# nRF24L01_-_ATmega328_test_board.net
KiCad netlist of a schematic drawn in EAGLE
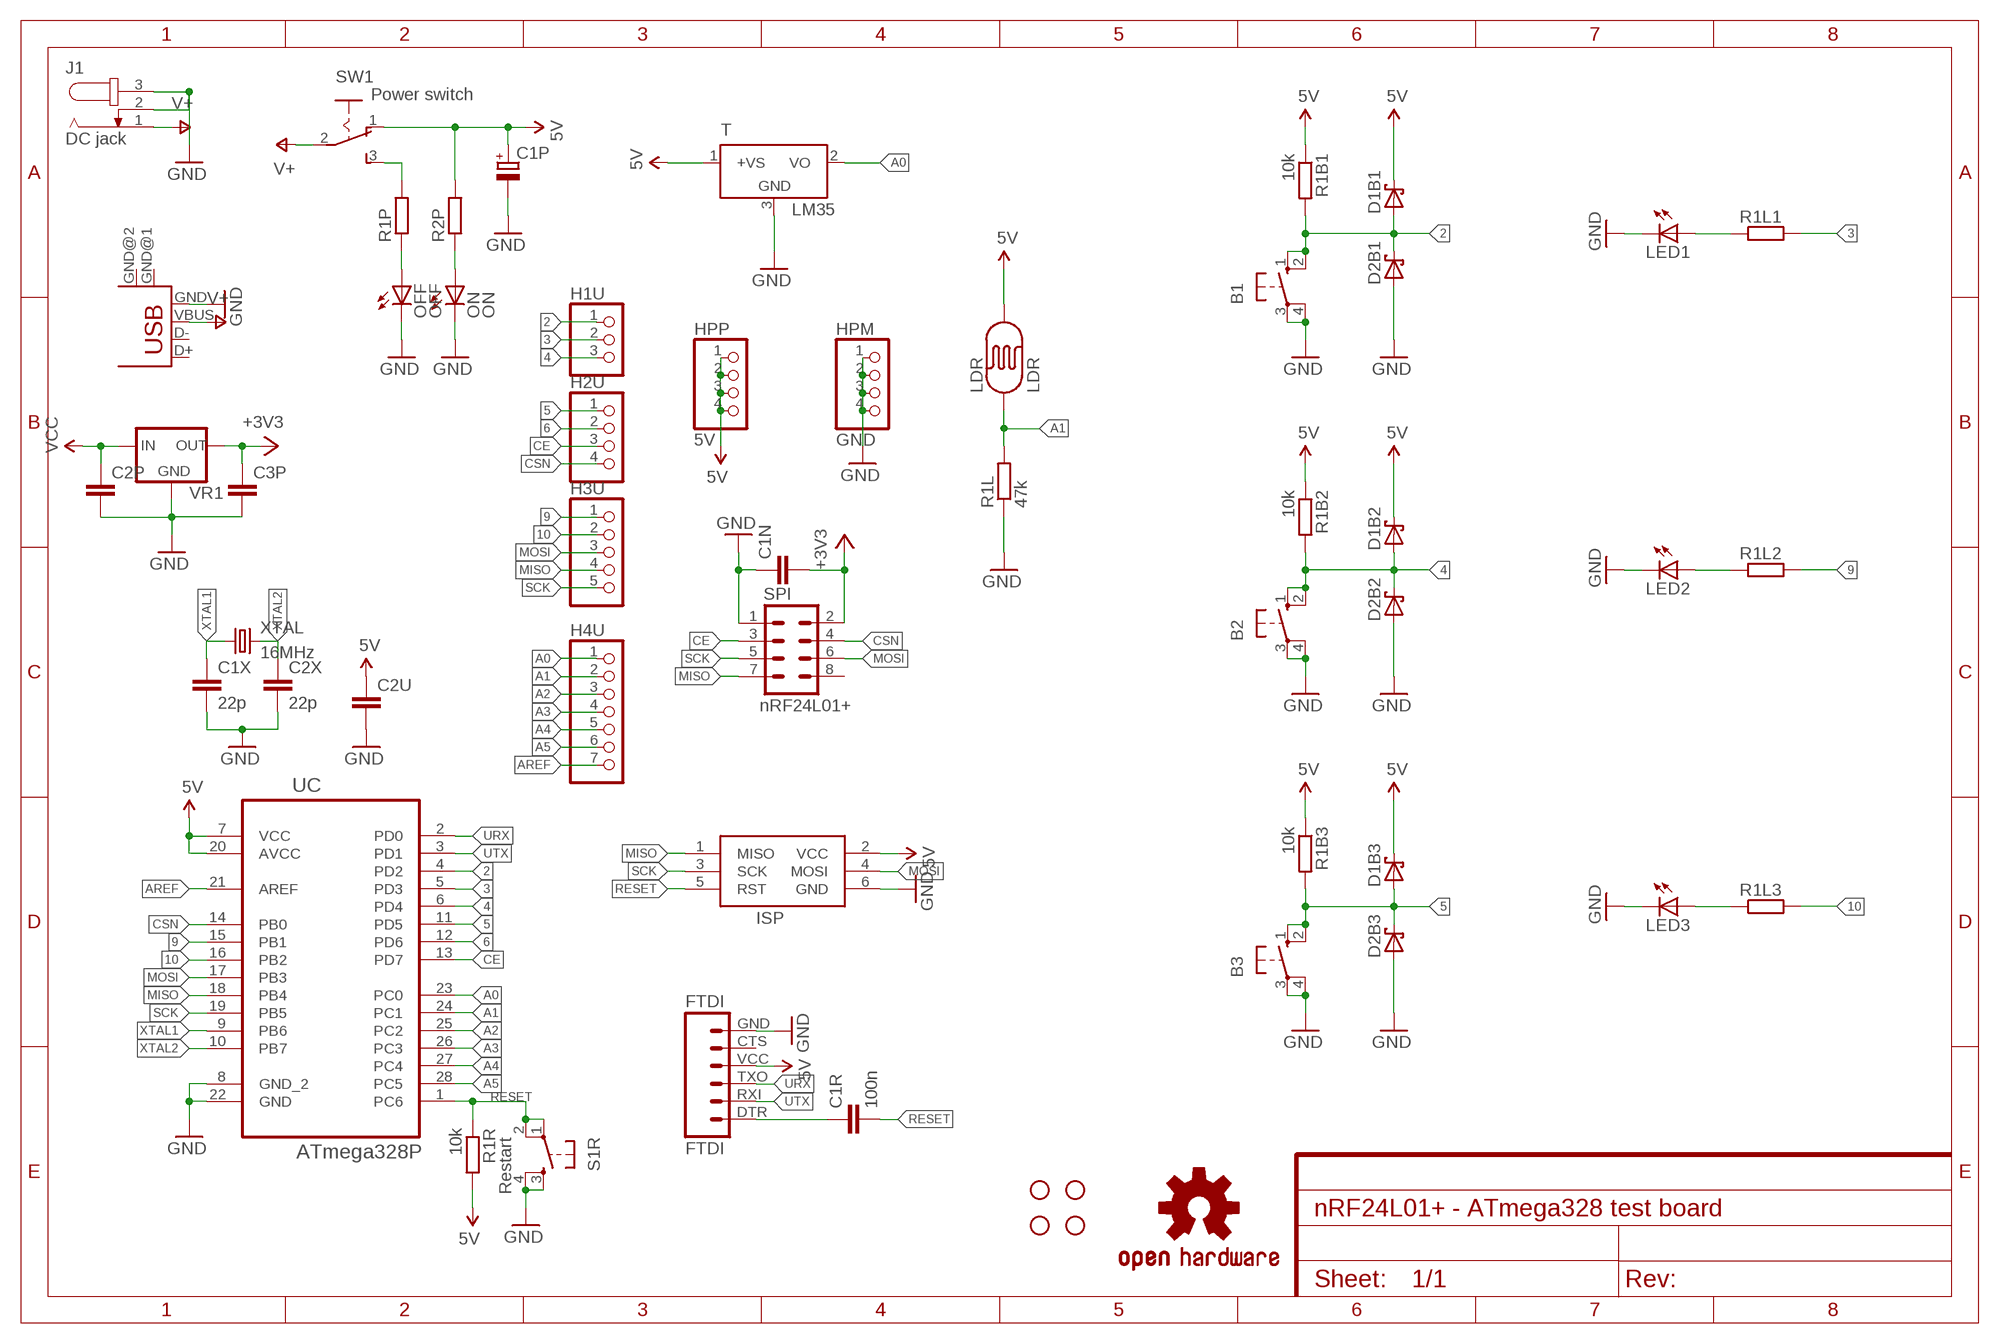
[diagram p0: schematic, sheet 1]

(export (version "E")
  (design (tool "Eeschema 10.0.6"))
  (components
    (comp (ref "B1")
      (value "40-XX")
      (footprint "eagle-import:B3F-40XX")
      (fields (field (name "MF") "OMRON COMPONENTS USA") (field (name "MPN") "B3F-4000"))
      (libsource (lib "eagle-import") (part "40-XX"))
    )
    (comp (ref "B2")
      (value "40-XX")
      (footprint "eagle-import:B3F-40XX")
      (fields (field (name "MF") "OMRON COMPONENTS USA") (field (name "MPN") "B3F-4000"))
      (libsource (lib "eagle-import") (part "40-XX"))
    )
    (comp (ref "B3")
      (value "40-XX")
      (footprint "eagle-import:B3F-40XX")
      (fields (field (name "MF") "OMRON COMPONENTS USA") (field (name "MPN") "B3F-4000"))
      (libsource (lib "eagle-import") (part "40-XX"))
    )
    (comp (ref "C1N")
      (value "C-EU050-025X075")
      (footprint "eagle-import:C050-025X075")
      (libsource (lib "eagle-import") (part "resistor_C-EU050-025X075"))
    )
    (comp (ref "C1P")
      (value "CPOL-EUE5-8.5")
      (footprint "eagle-import:E5-8,5")
      (libsource (lib "eagle-import") (part "CPOL-EUE5-8.5"))
    )
    (comp (ref "C1R")
      (value "100n")
      (footprint "eagle-import:C050-025X075")
      (libsource (lib "eagle-import") (part "resistor_C-EU050-025X075"))
    )
    (comp (ref "C1X")
      (value "22p")
      (footprint "eagle-import:C025-025X050")
      (libsource (lib "eagle-import") (part "resistor_C-EU025-025X050"))
    )
    (comp (ref "C2P")
      (value "C-EU050-025X075")
      (footprint "eagle-import:C050-025X075")
      (libsource (lib "eagle-import") (part "resistor_C-EU050-025X075"))
    )
    (comp (ref "C2U")
      (value "C-EU050-055X075")
      (footprint "eagle-import:C050-055X075")
      (libsource (lib "eagle-import") (part "C-EU050-055X075"))
    )
    (comp (ref "C2X")
      (value "22p")
      (footprint "eagle-import:C025-025X050")
      (libsource (lib "eagle-import") (part "resistor_C-EU025-025X050"))
    )
    (comp (ref "C3P")
      (value "C-EU050-025X075")
      (footprint "eagle-import:C050-025X075")
      (libsource (lib "eagle-import") (part "resistor_C-EU050-025X075"))
    )
    (comp (ref "D1B1")
      (value "SCHOTTKY-DIODEDO41-7")
      (footprint "eagle-import:DO41-7")
      (libsource (lib "eagle-import") (part "SCHOTTKY-DIODEDO41-7"))
    )
    (comp (ref "D1B2")
      (value "SCHOTTKY-DIODEDO41-7")
      (footprint "eagle-import:DO41-7")
      (libsource (lib "eagle-import") (part "SCHOTTKY-DIODEDO41-7"))
    )
    (comp (ref "D1B3")
      (value "SCHOTTKY-DIODEDO41-7")
      (footprint "eagle-import:DO41-7")
      (libsource (lib "eagle-import") (part "SCHOTTKY-DIODEDO41-7"))
    )
    (comp (ref "D2B1")
      (value "SCHOTTKY-DIODEDO41-7")
      (footprint "eagle-import:DO41-7")
      (libsource (lib "eagle-import") (part "SCHOTTKY-DIODEDO41-7"))
    )
    (comp (ref "D2B2")
      (value "SCHOTTKY-DIODEDO41-7")
      (footprint "eagle-import:DO41-7")
      (libsource (lib "eagle-import") (part "SCHOTTKY-DIODEDO41-7"))
    )
    (comp (ref "D2B3")
      (value "SCHOTTKY-DIODEDO41-7")
      (footprint "eagle-import:DO41-7")
      (libsource (lib "eagle-import") (part "SCHOTTKY-DIODEDO41-7"))
    )
    (comp (ref "FTDI")
      (value "FTDI")
      (footprint "eagle-import:FTDI_BASIC")
      (libsource (lib "eagle-import") (part "FTDI_BASICPTH"))
    )
    (comp (ref "H1")
      (value "STAND-OFF")
      (footprint "eagle-import:STAND-OFF")
      (libsource (lib "eagle-import") (part "STAND-OFF"))
    )
    (comp (ref "H1U")
      (value "PINHD-1X3")
      (footprint "eagle-import:1X03")
      (libsource (lib "eagle-import") (part "PINHD-1X3"))
    )
    (comp (ref "H2")
      (value "STAND-OFF")
      (footprint "eagle-import:STAND-OFF")
      (libsource (lib "eagle-import") (part "STAND-OFF"))
    )
    (comp (ref "H2U")
      (value "PINHD-1X4")
      (footprint "eagle-import:1X04")
      (libsource (lib "eagle-import") (part "PINHD-1X4"))
    )
    (comp (ref "H3")
      (value "STAND-OFF")
      (footprint "eagle-import:STAND-OFF")
      (libsource (lib "eagle-import") (part "STAND-OFF"))
    )
    (comp (ref "H3U")
      (value "PINHD-1X5")
      (footprint "eagle-import:1X05")
      (libsource (lib "eagle-import") (part "PINHD-1X5"))
    )
    (comp (ref "H4")
      (value "STAND-OFF")
      (footprint "eagle-import:STAND-OFF")
      (libsource (lib "eagle-import") (part "STAND-OFF"))
    )
    (comp (ref "H4U")
      (value "PINHD-1X7")
      (footprint "eagle-import:1X07")
      (libsource (lib "eagle-import") (part "PINHD-1X7"))
    )
    (comp (ref "HPM")
      (value "GND")
      (footprint "eagle-import:1X04")
      (libsource (lib "eagle-import") (part "PINHD-1X4"))
    )
    (comp (ref "HPP")
      (value "5V")
      (footprint "eagle-import:1X04")
      (libsource (lib "eagle-import") (part "PINHD-1X4"))
    )
    (comp (ref "ISP")
      (value "AVRISP-6")
      (footprint "eagle-import:AVRISP")
      (libsource (lib "eagle-import") (part "AVRISP-6"))
    )
    (comp (ref "J1")
      (value "DC jack")
      (footprint "eagle-import:SPC4078")
      (libsource (lib "eagle-import") (part "JACK-PLUG1"))
    )
    (comp (ref "J2")
      (value "USB mini")
      (footprint "eagle-import:USB-MB-H")
      (libsource (lib "eagle-import") (part "USB-MB-H"))
    )
    (comp (ref "LDR")
      (value "LDR")
      (footprint "eagle-import:PHOTOCELL")
      (libsource (lib "eagle-import") (part "PHOTOCELLPTH"))
    )
    (comp (ref "LED1")
      (value "LED5MM")
      (footprint "eagle-import:LED5MM")
      (libsource (lib "eagle-import") (part "LED5MM"))
    )
    (comp (ref "LED2")
      (value "LED5MM")
      (footprint "eagle-import:LED5MM")
      (libsource (lib "eagle-import") (part "LED5MM"))
    )
    (comp (ref "LED3")
      (value "LED5MM")
      (footprint "eagle-import:LED5MM")
      (libsource (lib "eagle-import") (part "LED5MM"))
    )
    (comp (ref "LOGO1")
      (value "OSHW-LOGOM-COPPER")
      (footprint "eagle-import:OSHW-LOGO-M_COPPER")
      (libsource (lib "eagle-import") (part "OSHW-LOGOM-COPPER"))
    )
    (comp (ref "OFF")
      (value "OFF")
      (footprint "eagle-import:LED3MM")
      (libsource (lib "eagle-import") (part "LED3MM"))
    )
    (comp (ref "ON")
      (value "ON")
      (footprint "eagle-import:LED3MM")
      (libsource (lib "eagle-import") (part "LED3MM"))
    )
    (comp (ref "R1B1")
      (value "10k")
      (footprint "eagle-import:0207_7")
      (libsource (lib "eagle-import") (part "R-EU_0207/7"))
    )
    (comp (ref "R1B2")
      (value "10k")
      (footprint "eagle-import:0207_7")
      (libsource (lib "eagle-import") (part "R-EU_0207/7"))
    )
    (comp (ref "R1B3")
      (value "10k")
      (footprint "eagle-import:0207_7")
      (libsource (lib "eagle-import") (part "R-EU_0207/7"))
    )
    (comp (ref "R1L")
      (value "47k")
      (footprint "eagle-import:0207_7")
      (libsource (lib "eagle-import") (part "R-EU_0207/7"))
    )
    (comp (ref "R1L1")
      (value "R-EU_0207/7")
      (footprint "eagle-import:0207_7")
      (libsource (lib "eagle-import") (part "R-EU_0207/7"))
    )
    (comp (ref "R1L2")
      (value "R-EU_0207/7")
      (footprint "eagle-import:0207_7")
      (libsource (lib "eagle-import") (part "R-EU_0207/7"))
    )
    (comp (ref "R1L3")
      (value "R-EU_0207/7")
      (footprint "eagle-import:0207_7")
      (libsource (lib "eagle-import") (part "R-EU_0207/7"))
    )
    (comp (ref "R1P")
      (value "R-EU_0207/7")
      (footprint "eagle-import:0207_7")
      (libsource (lib "eagle-import") (part "R-EU_0207/7"))
    )
    (comp (ref "R1R")
      (value "10k")
      (footprint "eagle-import:0207_7")
      (libsource (lib "eagle-import") (part "R-EU_0207/7"))
    )
    (comp (ref "R2P")
      (value "R-EU_0207/7")
      (footprint "eagle-import:0207_7")
      (libsource (lib "eagle-import") (part "R-EU_0207/7"))
    )
    (comp (ref "S1R")
      (value "Restart")
      (footprint "eagle-import:TACTILE-PTH")
      (libsource (lib "eagle-import") (part "TAC_SWITCHPTH"))
    )
    (comp (ref "SPI")
      (value "nRF24L01+")
      (footprint "eagle-import:2X4")
      (fields (field (name "MF") "OLIMEX") (field (name "MPN") "MOD-NRF24LR"))
      (libsource (lib "eagle-import") (part "M04X2"))
    )
    (comp (ref "SW1")
      (value "Power switch")
      (footprint "eagle-import:SWITCH_2MM")
      (libsource (lib "eagle-import") (part "SPDT_SWITCH_2MM"))
    )
    (comp (ref "T")
      (value "LM35")
      (footprint "eagle-import:TO92")
      (libsource (lib "eagle-import") (part "LM35CZ"))
    )
    (comp (ref "UC")
      (value "ATmega328P")
      (footprint "eagle-import:DIP254P762X457-28")
      (fields (field (name "MPN") "ATMEGA328P-PU"))
      (libsource (lib "eagle-import") (part "ATMEGA328P-PU"))
    )
    (comp (ref "VR1")
      (value "78LXX")
      (footprint "eagle-import:78LXX")
      (libsource (lib "eagle-import") (part "78LXX"))
    )
    (comp (ref "XTAL")
      (value "16MHz")
      (footprint "eagle-import:HC49_S")
      (libsource (lib "eagle-import") (part "CRYSTALHC49S"))
    )
  )
  (nets
    (net (code "1") (name "+3V3") (class "Default")
      (node (ref "C1N") (pin "2") (pinfunction "2_2") (pintype "passive"))
      (node (ref "C3P") (pin "1") (pinfunction "1_1") (pintype "passive"))
      (node (ref "SPI") (pin "2") (pinfunction "2_2") (pintype "passive"))
      (node (ref "VR1") (pin "OUT") (pinfunction "OUT_OUT") (pintype "passive"))
    )
    (net (code "2") (name "2") (class "Default")
      (node (ref "B1") (pin "1") (pinfunction "S_1") (pintype "passive"))
      (node (ref "B1") (pin "2") (pinfunction "S1_2") (pintype "passive"))
      (node (ref "D1B1") (pin "A") (pinfunction "A_A") (pintype "passive"))
      (node (ref "D2B1") (pin "C") (pinfunction "C_C") (pintype "passive"))
      (node (ref "H1U") (pin "1") (pinfunction "1_1") (pintype "passive"))
      (node (ref "R1B1") (pin "2") (pinfunction "2_2") (pintype "passive"))
      (node (ref "UC") (pin "4") (pinfunction "PD2_4") (pintype "bidirectional"))
    )
    (net (code "3") (name "3") (class "Default")
      (node (ref "H1U") (pin "2") (pinfunction "2_2") (pintype "passive"))
      (node (ref "R1L1") (pin "2") (pinfunction "2_2") (pintype "passive"))
      (node (ref "UC") (pin "5") (pinfunction "PD3_5") (pintype "bidirectional"))
    )
    (net (code "4") (name "4") (class "Default")
      (node (ref "B2") (pin "1") (pinfunction "S_1") (pintype "passive"))
      (node (ref "B2") (pin "2") (pinfunction "S1_2") (pintype "passive"))
      (node (ref "D1B2") (pin "A") (pinfunction "A_A") (pintype "passive"))
      (node (ref "D2B2") (pin "C") (pinfunction "C_C") (pintype "passive"))
      (node (ref "H1U") (pin "3") (pinfunction "3_3") (pintype "passive"))
      (node (ref "R1B2") (pin "2") (pinfunction "2_2") (pintype "passive"))
      (node (ref "UC") (pin "6") (pinfunction "PD4_6") (pintype "bidirectional"))
    )
    (net (code "5") (name "5") (class "Default")
      (node (ref "B3") (pin "1") (pinfunction "S_1") (pintype "passive"))
      (node (ref "B3") (pin "2") (pinfunction "S1_2") (pintype "passive"))
      (node (ref "D1B3") (pin "A") (pinfunction "A_A") (pintype "passive"))
      (node (ref "D2B3") (pin "C") (pinfunction "C_C") (pintype "passive"))
      (node (ref "H2U") (pin "1") (pinfunction "1_1") (pintype "passive"))
      (node (ref "R1B3") (pin "2") (pinfunction "2_2") (pintype "passive"))
      (node (ref "UC") (pin "11") (pinfunction "PD5_11") (pintype "bidirectional"))
    )
    (net (code "6") (name "5V") (class "Default")
      (node (ref "C1P") (pin "+") (pinfunction "+_+") (pintype "passive"))
      (node (ref "C2U") (pin "1") (pinfunction "1_1") (pintype "passive"))
      (node (ref "D1B1") (pin "C") (pinfunction "C_C") (pintype "passive"))
      (node (ref "D1B2") (pin "C") (pinfunction "C_C") (pintype "passive"))
      (node (ref "D1B3") (pin "C") (pinfunction "C_C") (pintype "passive"))
      (node (ref "FTDI") (pin "VCC") (pinfunction "4_VCC") (pintype "passive"))
      (node (ref "HPP") (pin "1") (pinfunction "1_1") (pintype "passive"))
      (node (ref "HPP") (pin "2") (pinfunction "2_2") (pintype "passive"))
      (node (ref "HPP") (pin "3") (pinfunction "3_3") (pintype "passive"))
      (node (ref "HPP") (pin "4") (pinfunction "4_4") (pintype "passive"))
      (node (ref "ISP") (pin "2") (pinfunction "VCC_2") (pintype "power_in"))
      (node (ref "LDR") (pin "2") (pinfunction "P$2_2") (pintype "bidirectional"))
      (node (ref "R1B1") (pin "1") (pinfunction "1_1") (pintype "passive"))
      (node (ref "R1B2") (pin "1") (pinfunction "1_1") (pintype "passive"))
      (node (ref "R1B3") (pin "1") (pinfunction "1_1") (pintype "passive"))
      (node (ref "R1R") (pin "2") (pinfunction "2_2") (pintype "passive"))
      (node (ref "R2P") (pin "2") (pinfunction "2_2") (pintype "passive"))
      (node (ref "SW1") (pin "1") (pinfunction "1_1") (pintype "passive"))
      (node (ref "T") (pin "1") (pinfunction "+VS_1") (pintype "input"))
      (node (ref "UC") (pin "20") (pinfunction "AVCC_20") (pintype "power_in"))
      (node (ref "UC") (pin "7") (pinfunction "VCC_7") (pintype "power_in"))
    )
    (net (code "7") (name "6") (class "Default")
      (node (ref "H2U") (pin "2") (pinfunction "2_2") (pintype "passive"))
      (node (ref "UC") (pin "12") (pinfunction "PD6_12") (pintype "bidirectional"))
    )
    (net (code "8") (name "9") (class "Default")
      (node (ref "H3U") (pin "1") (pinfunction "1_1") (pintype "passive"))
      (node (ref "R1L2") (pin "2") (pinfunction "2_2") (pintype "passive"))
      (node (ref "UC") (pin "15") (pinfunction "PB1_15") (pintype "bidirectional"))
    )
    (net (code "9") (name "10") (class "Default")
      (node (ref "H3U") (pin "2") (pinfunction "2_2") (pintype "passive"))
      (node (ref "R1L3") (pin "2") (pinfunction "2_2") (pintype "passive"))
      (node (ref "UC") (pin "16") (pinfunction "PB2_16") (pintype "bidirectional"))
    )
    (net (code "10") (name "A0") (class "Default")
      (node (ref "H4U") (pin "1") (pinfunction "1_1") (pintype "passive"))
      (node (ref "T") (pin "2") (pinfunction "VO_2") (pintype "input"))
      (node (ref "UC") (pin "23") (pinfunction "PC0_23") (pintype "bidirectional"))
    )
    (net (code "11") (name "A1") (class "Default")
      (node (ref "H4U") (pin "2") (pinfunction "2_2") (pintype "passive"))
      (node (ref "LDR") (pin "1") (pinfunction "P$1_1") (pintype "bidirectional"))
      (node (ref "R1L") (pin "2") (pinfunction "2_2") (pintype "passive"))
      (node (ref "UC") (pin "24") (pinfunction "PC1_24") (pintype "bidirectional"))
    )
    (net (code "12") (name "A2") (class "Default")
      (node (ref "H4U") (pin "3") (pinfunction "3_3") (pintype "passive"))
      (node (ref "UC") (pin "25") (pinfunction "PC2_25") (pintype "bidirectional"))
    )
    (net (code "13") (name "A3") (class "Default")
      (node (ref "H4U") (pin "4") (pinfunction "4_4") (pintype "passive"))
      (node (ref "UC") (pin "26") (pinfunction "PC3_26") (pintype "bidirectional"))
    )
    (net (code "14") (name "A4") (class "Default")
      (node (ref "H4U") (pin "5") (pinfunction "5_5") (pintype "passive"))
      (node (ref "UC") (pin "27") (pinfunction "PC4_27") (pintype "bidirectional"))
    )
    (net (code "15") (name "A5") (class "Default")
      (node (ref "H4U") (pin "6") (pinfunction "6_6") (pintype "passive"))
      (node (ref "UC") (pin "28") (pinfunction "PC5_28") (pintype "bidirectional"))
    )
    (net (code "16") (name "AREF") (class "Default")
      (node (ref "H4U") (pin "7") (pinfunction "7_7") (pintype "passive"))
      (node (ref "UC") (pin "21") (pinfunction "AREF_21") (pintype "input"))
    )
    (net (code "17") (name "CE") (class "Default")
      (node (ref "H2U") (pin "3") (pinfunction "3_3") (pintype "passive"))
      (node (ref "SPI") (pin "3") (pinfunction "3_3") (pintype "passive"))
      (node (ref "UC") (pin "13") (pinfunction "PD7_13") (pintype "bidirectional"))
    )
    (net (code "18") (name "CSN") (class "Default")
      (node (ref "H2U") (pin "4") (pinfunction "4_4") (pintype "passive"))
      (node (ref "SPI") (pin "4") (pinfunction "4_4") (pintype "passive"))
      (node (ref "UC") (pin "14") (pinfunction "PB0_14") (pintype "bidirectional"))
    )
    (net (code "19") (name "GND") (class "Default")
      (node (ref "B1") (pin "3") (pinfunction "P_3") (pintype "passive"))
      (node (ref "B1") (pin "4") (pinfunction "P1_4") (pintype "passive"))
      (node (ref "B2") (pin "3") (pinfunction "P_3") (pintype "passive"))
      (node (ref "B2") (pin "4") (pinfunction "P1_4") (pintype "passive"))
      (node (ref "B3") (pin "3") (pinfunction "P_3") (pintype "passive"))
      (node (ref "B3") (pin "4") (pinfunction "P1_4") (pintype "passive"))
      (node (ref "C1N") (pin "1") (pinfunction "1_1") (pintype "passive"))
      (node (ref "C1P") (pin "-") (pinfunction "-_-") (pintype "passive"))
      (node (ref "C1X") (pin "2") (pinfunction "2_2") (pintype "passive"))
      (node (ref "C2P") (pin "2") (pinfunction "2_2") (pintype "passive"))
      (node (ref "C2U") (pin "2") (pinfunction "2_2") (pintype "passive"))
      (node (ref "C2X") (pin "2") (pinfunction "2_2") (pintype "passive"))
      (node (ref "C3P") (pin "2") (pinfunction "2_2") (pintype "passive"))
      (node (ref "D2B1") (pin "A") (pinfunction "A_A") (pintype "passive"))
      (node (ref "D2B2") (pin "A") (pinfunction "A_A") (pintype "passive"))
      (node (ref "D2B3") (pin "A") (pinfunction "A_A") (pintype "passive"))
      (node (ref "FTDI") (pin "GND") (pinfunction "6_GND") (pintype "passive"))
      (node (ref "HPM") (pin "1") (pinfunction "1_1") (pintype "passive"))
      (node (ref "HPM") (pin "2") (pinfunction "2_2") (pintype "passive"))
      (node (ref "HPM") (pin "3") (pinfunction "3_3") (pintype "passive"))
      (node (ref "HPM") (pin "4") (pinfunction "4_4") (pintype "passive"))
      (node (ref "ISP") (pin "6") (pinfunction "GND_6") (pintype "power_in"))
      (node (ref "J1") (pin "2") (pinfunction "2_2") (pintype "passive"))
      (node (ref "J1") (pin "3") (pinfunction "3_3") (pintype "passive"))
      (node (ref "J2") (pin "GND") (pinfunction "GND_GND") (pintype "bidirectional"))
      (node (ref "LED1") (pin "K") (pinfunction "C_K") (pintype "passive"))
      (node (ref "LED2") (pin "K") (pinfunction "C_K") (pintype "passive"))
      (node (ref "LED3") (pin "K") (pinfunction "C_K") (pintype "passive"))
      (node (ref "OFF") (pin "K") (pinfunction "C_K") (pintype "passive"))
      (node (ref "ON") (pin "K") (pinfunction "C_K") (pintype "passive"))
      (node (ref "R1L") (pin "1") (pinfunction "1_1") (pintype "passive"))
      (node (ref "S1R") (pin "3") (pinfunction "3_3") (pintype "passive"))
      (node (ref "S1R") (pin "4") (pinfunction "4_4") (pintype "passive"))
      (node (ref "SPI") (pin "1") (pinfunction "1_1") (pintype "passive"))
      (node (ref "T") (pin "3") (pinfunction "GND_3") (pintype "power_in"))
      (node (ref "UC") (pin "22") (pinfunction "GND_22") (pintype "passive"))
      (node (ref "UC") (pin "8") (pinfunction "GND_2_8") (pintype "passive"))
      (node (ref "VR1") (pin "GND") (pinfunction "GND_GND") (pintype "input"))
    )
    (net (code "20") (name "MISO") (class "Default")
      (node (ref "H3U") (pin "4") (pinfunction "4_4") (pintype "passive"))
      (node (ref "ISP") (pin "1") (pinfunction "MISO_1") (pintype "input"))
      (node (ref "SPI") (pin "7") (pinfunction "7_7") (pintype "passive"))
      (node (ref "UC") (pin "18") (pinfunction "PB4_18") (pintype "bidirectional"))
    )
    (net (code "21") (name "MOSI") (class "Default")
      (node (ref "H3U") (pin "3") (pinfunction "3_3") (pintype "passive"))
      (node (ref "ISP") (pin "4") (pinfunction "MOSI_4") (pintype "output"))
      (node (ref "SPI") (pin "6") (pinfunction "6_6") (pintype "passive"))
      (node (ref "UC") (pin "17") (pinfunction "PB3_17") (pintype "bidirectional"))
    )
    (net (code "22") (name "Net-(FTDI-1)") (class "Default")
      (node (ref "C1R") (pin "1") (pinfunction "1_1") (pintype "passive"))
      (node (ref "FTDI") (pin "DTR") (pinfunction "1_DTR") (pintype "passive"))
    )
    (net (code "23") (name "Net-(LED1-PadA)") (class "Default")
      (node (ref "LED1") (pin "A") (pinfunction "A_A") (pintype "passive"))
      (node (ref "R1L1") (pin "1") (pinfunction "1_1") (pintype "passive"))
    )
    (net (code "24") (name "Net-(LED2-PadA)") (class "Default")
      (node (ref "LED2") (pin "A") (pinfunction "A_A") (pintype "passive"))
      (node (ref "R1L2") (pin "1") (pinfunction "1_1") (pintype "passive"))
    )
    (net (code "25") (name "Net-(LED3-PadA)") (class "Default")
      (node (ref "LED3") (pin "A") (pinfunction "A_A") (pintype "passive"))
      (node (ref "R1L3") (pin "1") (pinfunction "1_1") (pintype "passive"))
    )
    (net (code "26") (name "Net-(OFF-PadA)") (class "Default")
      (node (ref "OFF") (pin "A") (pinfunction "A_A") (pintype "passive"))
      (node (ref "R1P") (pin "1") (pinfunction "1_1") (pintype "passive"))
    )
    (net (code "27") (name "Net-(ON-PadA)") (class "Default")
      (node (ref "ON") (pin "A") (pinfunction "A_A") (pintype "passive"))
      (node (ref "R2P") (pin "1") (pinfunction "1_1") (pintype "passive"))
    )
    (net (code "28") (name "Net-(R1P-Pad2)") (class "Default")
      (node (ref "R1P") (pin "2") (pinfunction "2_2") (pintype "passive"))
      (node (ref "SW1") (pin "3") (pinfunction "3_3") (pintype "passive"))
    )
    (net (code "29") (name "RESET") (class "Default")
      (node (ref "C1R") (pin "2") (pinfunction "2_2") (pintype "passive"))
      (node (ref "ISP") (pin "5") (pinfunction "RST_5") (pintype "output"))
      (node (ref "R1R") (pin "1") (pinfunction "1_1") (pintype "passive"))
      (node (ref "S1R") (pin "1") (pinfunction "1_1") (pintype "passive"))
      (node (ref "S1R") (pin "2") (pinfunction "2_2") (pintype "passive"))
      (node (ref "UC") (pin "1") (pinfunction "PC6_1") (pintype "bidirectional"))
    )
    (net (code "30") (name "SCK") (class "Default")
      (node (ref "H3U") (pin "5") (pinfunction "5_5") (pintype "passive"))
      (node (ref "ISP") (pin "3") (pinfunction "SCK_3") (pintype "output"))
      (node (ref "SPI") (pin "5") (pinfunction "5_5") (pintype "passive"))
      (node (ref "UC") (pin "19") (pinfunction "PB5_19") (pintype "bidirectional"))
    )
    (net (code "31") (name "URX") (class "Default")
      (node (ref "FTDI") (pin "TXO") (pinfunction "3_TXO") (pintype "passive"))
      (node (ref "UC") (pin "2") (pinfunction "PD0_2") (pintype "bidirectional"))
    )
    (net (code "32") (name "UTX") (class "Default")
      (node (ref "FTDI") (pin "RXI") (pinfunction "2_RXI") (pintype "passive"))
      (node (ref "UC") (pin "3") (pinfunction "PD1_3") (pintype "bidirectional"))
    )
    (net (code "33") (name "V+") (class "Default")
      (node (ref "J1") (pin "1") (pinfunction "1_1") (pintype "passive"))
      (node (ref "J2") (pin "VBUS") (pinfunction "VBUS_VBUS") (pintype "bidirectional"))
      (node (ref "SW1") (pin "2") (pinfunction "2_2") (pintype "passive"))
    )
    (net (code "34") (name "VCC") (class "Default")
      (node (ref "C2P") (pin "1") (pinfunction "1_1") (pintype "passive"))
      (node (ref "VR1") (pin "IN") (pinfunction "IN_IN") (pintype "input"))
    )
    (net (code "35") (name "XTAL1") (class "Default")
      (node (ref "C1X") (pin "1") (pinfunction "1_1") (pintype "passive"))
      (node (ref "UC") (pin "9") (pinfunction "PB6_9") (pintype "bidirectional"))
      (node (ref "XTAL") (pin "1") (pinfunction "1_1") (pintype "passive"))
    )
    (net (code "36") (name "XTAL2") (class "Default")
      (node (ref "C2X") (pin "1") (pinfunction "1_1") (pintype "passive"))
      (node (ref "UC") (pin "10") (pinfunction "PB7_10") (pintype "bidirectional"))
      (node (ref "XTAL") (pin "2") (pinfunction "2_2") (pintype "passive"))
    )
    (net (code "37") (name "unconnected-(FTDI-5-PadCTS)") (class "Default")
      (node (ref "FTDI") (pin "CTS") (pinfunction "5_CTS") (pintype "passive"))
    )
    (net (code "38") (name "unconnected-(J2-GND-PadGND@1)") (class "Default")
      (node (ref "J2") (pin "GND@1") (pinfunction "GND_GND@1") (pintype "bidirectional"))
    )
    (net (code "39") (name "unconnected-(J2-GND-PadGND@2)") (class "Default")
      (node (ref "J2") (pin "GND@2") (pinfunction "GND_GND@2") (pintype "bidirectional"))
    )
    (net (code "40") (name "unconnected-(J2-PadD+)") (class "Default")
      (node (ref "J2") (pin "D+") (pinfunction "D+_D+") (pintype "bidirectional"))
    )
    (net (code "41") (name "unconnected-(J2-PadD-)") (class "Default")
      (node (ref "J2") (pin "D-") (pinfunction "D-_D-") (pintype "bidirectional"))
    )
    (net (code "42") (name "unconnected-(SPI-Pad8)") (class "Default")
      (node (ref "SPI") (pin "8") (pinfunction "8_8") (pintype "passive"))
    )
  )
)
